# KONNEKTING_HW1_1_Rev0.net
KiCad netlist of a schematic drawn in EAGLE
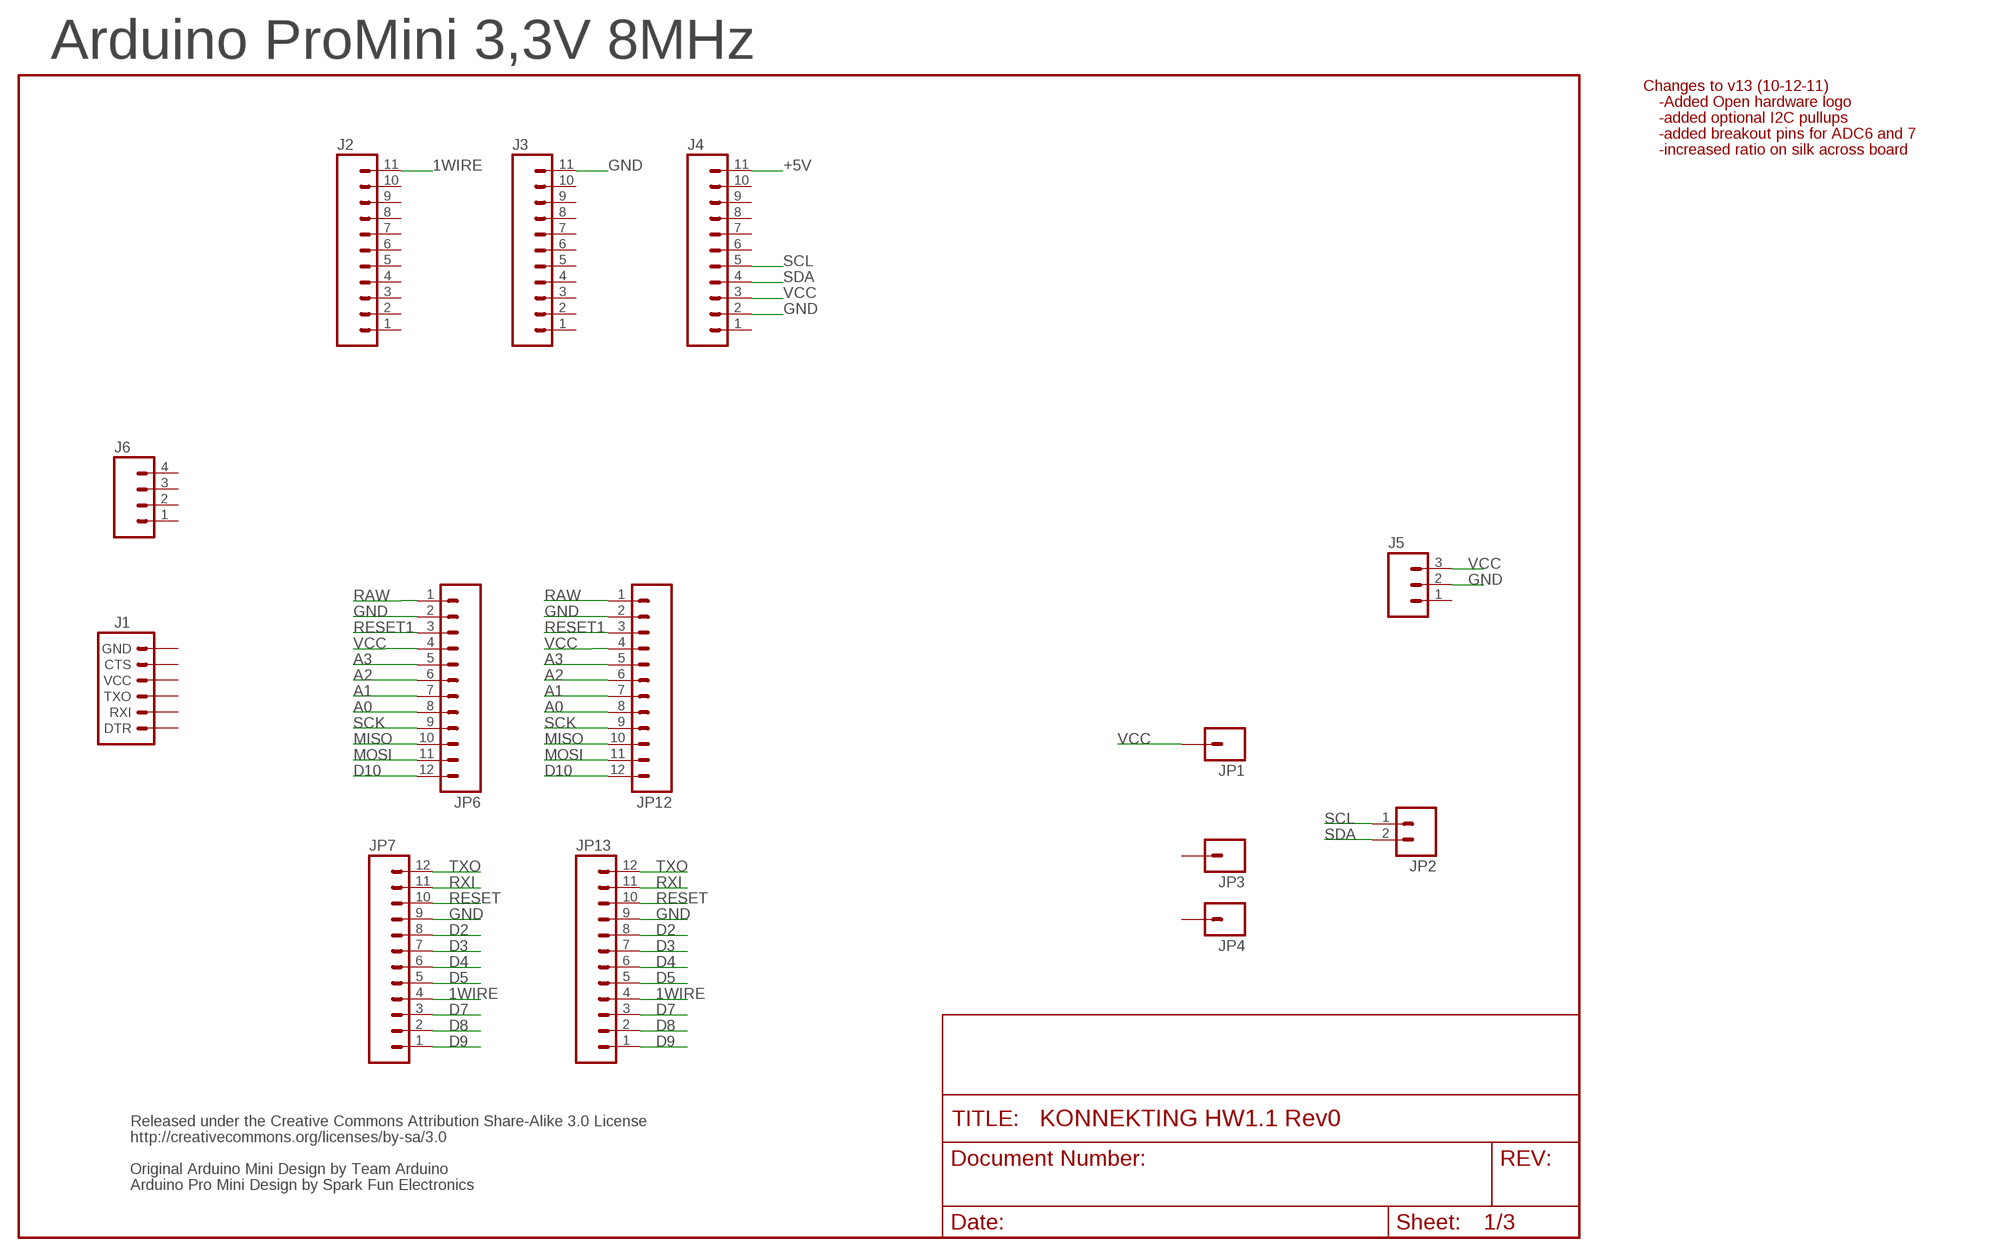
[diagram p0: schematic, sheet 1]
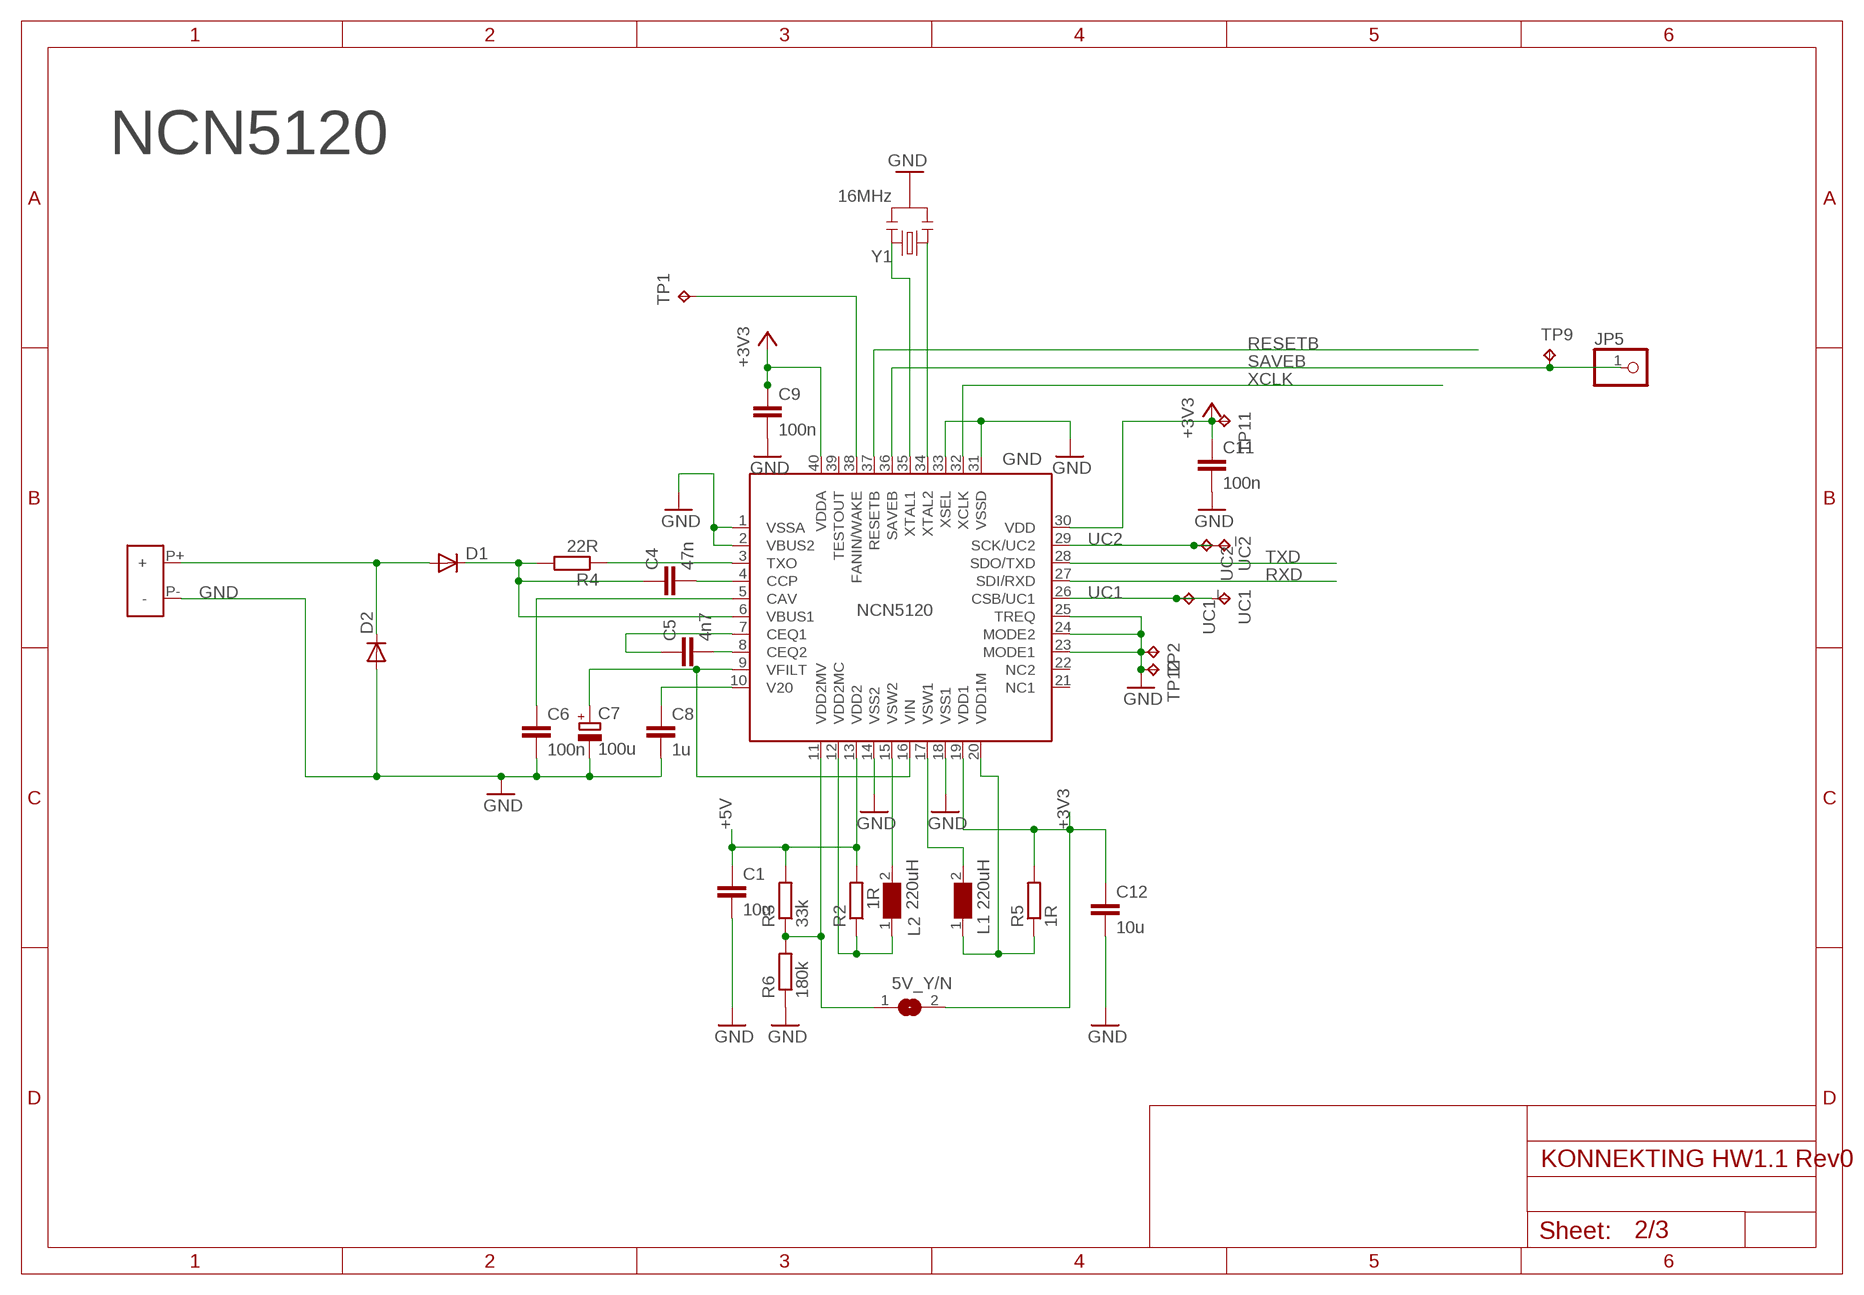
[diagram p1: schematic, sheet 2]
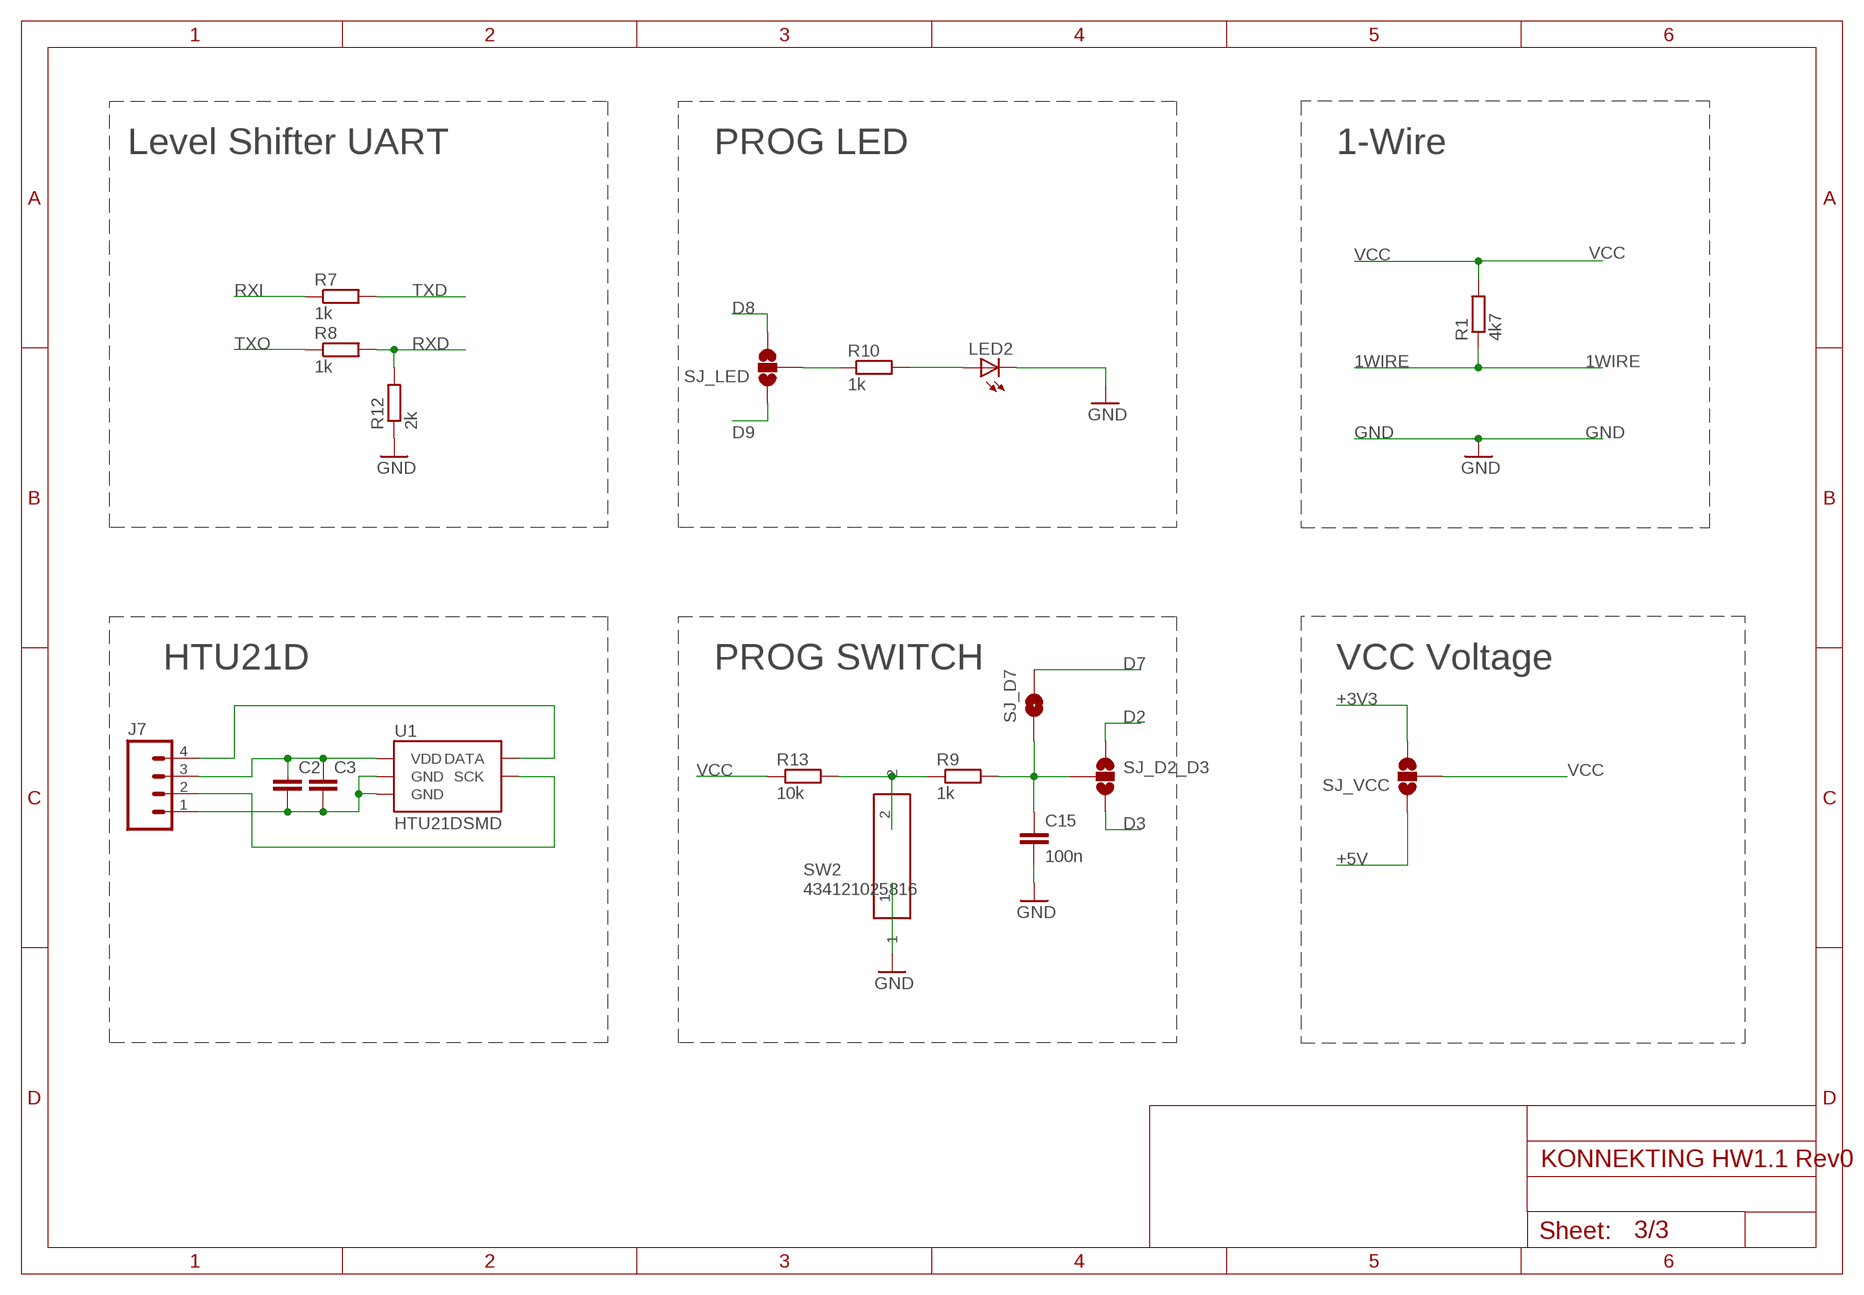
[diagram p2: schematic, sheet 3]

(export (version "E")
  (design (tool "Eeschema 10.0.6"))
  (components
    (comp (ref "J1")
      (value "ARDUINO_SERIAL_PROGRAMPTH")
      (footprint "eagle-import:1X06")
      (libsource (lib "eagle-import") (part "ARDUINO_SERIAL_PROGRAMPTH"))
    )
    (comp (ref "J2")
      (value "M11PTH")
      (footprint "eagle-import:1X11")
      (libsource (lib "eagle-import") (part "M11PTH"))
    )
    (comp (ref "J3")
      (value "M11PTH")
      (footprint "eagle-import:1X11")
      (libsource (lib "eagle-import") (part "M11PTH"))
    )
    (comp (ref "J4")
      (value "M11PTH")
      (footprint "eagle-import:1X11")
      (libsource (lib "eagle-import") (part "M11PTH"))
    )
    (comp (ref "J5")
      (value "M03PTH")
      (footprint "eagle-import:1X03")
      (libsource (lib "eagle-import") (part "M03PTH"))
    )
    (comp (ref "J6")
      (value "M04PTH")
      (footprint "eagle-import:1X04")
      (libsource (lib "eagle-import") (part "M04PTH"))
    )
    (comp (ref "JP1")
      (value "M01PTH")
      (footprint "eagle-import:1X01")
      (libsource (lib "eagle-import") (part "M01PTH"))
    )
    (comp (ref "JP2")
      (value "M02PTH")
      (footprint "eagle-import:1X02")
      (libsource (lib "eagle-import") (part "M02PTH"))
    )
    (comp (ref "JP3")
      (value "M01PTH")
      (footprint "eagle-import:1X01")
      (libsource (lib "eagle-import") (part "M01PTH"))
    )
    (comp (ref "JP4")
      (value "M01PTH")
      (footprint "eagle-import:1X01")
      (libsource (lib "eagle-import") (part "M01PTH"))
    )
    (comp (ref "JP6")
      (value "M12PTH")
      (footprint "eagle-import:1X12")
      (libsource (lib "eagle-import") (part "M12PTH"))
    )
    (comp (ref "JP7")
      (value "M12PTH")
      (footprint "eagle-import:1X12")
      (libsource (lib "eagle-import") (part "M12PTH"))
    )
    (comp (ref "JP12")
      (value "M12PTH")
      (footprint "eagle-import:1X12")
      (libsource (lib "eagle-import") (part "M12PTH"))
    )
    (comp (ref "JP13")
      (value "M12PTH")
      (footprint "eagle-import:1X12")
      (libsource (lib "eagle-import") (part "M12PTH"))
    )
    (comp (ref "C2")
      (value "CAP0603-CAP")
      (footprint "eagle-import:0603-CAP")
      (libsource (lib "eagle-import") (part "CAP0603-CAP"))
    )
    (comp (ref "C3")
      (value "CAP0603-CAP")
      (footprint "eagle-import:0603-CAP")
      (libsource (lib "eagle-import") (part "CAP0603-CAP"))
    )
    (comp (ref "C15")
      (value "100n")
      (footprint "eagle-import:C0603")
      (libsource (lib "eagle-import") (part "C-EUC0603"))
    )
    (comp (ref "J7")
      (value "M04PTH")
      (footprint "eagle-import:1X04")
      (libsource (lib "eagle-import") (part "M04PTH"))
    )
    (comp (ref "LED2")
      (value "LEDCHIP-LED0805")
      (footprint "eagle-import:CHIP-LED0805")
      (libsource (lib "eagle-import") (part "LEDCHIP-LED0805"))
    )
    (comp (ref "R1")
      (value "4k7")
      (footprint "eagle-import:R0603")
      (libsource (lib "eagle-import") (part "R-EU_R0603"))
    )
    (comp (ref "R7")
      (value "1k")
      (footprint "eagle-import:R0805")
      (libsource (lib "eagle-import") (part "R-EU_R0805"))
    )
    (comp (ref "R8")
      (value "1k")
      (footprint "eagle-import:R0805")
      (libsource (lib "eagle-import") (part "R-EU_R0805"))
    )
    (comp (ref "R9")
      (value "1k")
      (footprint "eagle-import:R0603")
      (libsource (lib "eagle-import") (part "R-EU_R0603"))
    )
    (comp (ref "R10")
      (value "1k")
      (footprint "eagle-import:R0603")
      (libsource (lib "eagle-import") (part "R-EU_R0603"))
    )
    (comp (ref "R12")
      (value "2k")
      (footprint "eagle-import:R0805")
      (libsource (lib "eagle-import") (part "R-EU_R0805"))
    )
    (comp (ref "R13")
      (value "10k")
      (footprint "eagle-import:R0603")
      (libsource (lib "eagle-import") (part "R-EU_R0603"))
    )
    (comp (ref "SJ_D2_D3")
      (value "SOLDERJUMPER_2WAYS")
      (footprint "eagle-import:SJ_3")
      (libsource (lib "eagle-import") (part "SOLDERJUMPER_2WAYS"))
    )
    (comp (ref "SJ_D7")
      (value "SOLDERJUMPERNO")
      (footprint "eagle-import:SJ_2S-NO")
      (libsource (lib "eagle-import") (part "SOLDERJUMPERNO"))
    )
    (comp (ref "SJ_LED")
      (value "SOLDERJUMPER_2WAYS")
      (footprint "eagle-import:SJ_3")
      (libsource (lib "eagle-import") (part "SOLDERJUMPER_2WAYS"))
    )
    (comp (ref "SJ_VCC")
      (value "SOLDERJUMPER_2WAYS")
      (footprint "eagle-import:SJ_3")
      (libsource (lib "eagle-import") (part "SOLDERJUMPER_2WAYS"))
    )
    (comp (ref "SW2")
      (value "434121025816")
      (footprint "eagle-import:434121025816")
      (libsource (lib "eagle-import") (part "434121025816"))
    )
    (comp (ref "U1")
      (value "HTU21DSMD")
      (footprint "eagle-import:HTU21D")
      (libsource (lib "eagle-import") (part "HTU21DSMD"))
    )
    (comp (ref "5V_Y/N")
      (value "SJ")
      (footprint "eagle-import:SJ")
      (libsource (lib "eagle-import") (part "SJ"))
    )
    (comp (ref "C1")
      (value "10u")
      (footprint "eagle-import:C0805")
      (libsource (lib "eagle-import") (part "C-EUC0805"))
    )
    (comp (ref "C4")
      (value "47n")
      (footprint "eagle-import:C0603")
      (libsource (lib "eagle-import") (part "C-EUC0603"))
    )
    (comp (ref "C5")
      (value "4n7")
      (footprint "eagle-import:C0603")
      (libsource (lib "eagle-import") (part "C-EUC0603"))
    )
    (comp (ref "C6")
      (value "100n")
      (footprint "eagle-import:C0603")
      (libsource (lib "eagle-import") (part "C-EUC0603"))
    )
    (comp (ref "C7")
      (value "100u")
      (footprint "eagle-import:UD-6,3X7,7_NICHICON")
      (libsource (lib "eagle-import") (part "CPOL-EUUD-6,3X7,7"))
    )
    (comp (ref "C8")
      (value "1u")
      (footprint "eagle-import:C0603")
      (libsource (lib "eagle-import") (part "C-EUC0603"))
    )
    (comp (ref "C9")
      (value "100n")
      (footprint "eagle-import:C0603")
      (libsource (lib "eagle-import") (part "C-EUC0603"))
    )
    (comp (ref "C11")
      (value "100n")
      (footprint "eagle-import:C0603")
      (libsource (lib "eagle-import") (part "C-EUC0603"))
    )
    (comp (ref "C12")
      (value "10u")
      (footprint "eagle-import:C0805")
      (libsource (lib "eagle-import") (part "C-EUC0805"))
    )
    (comp (ref "D1")
      (value "DIODESMA-ALT")
      (footprint "eagle-import:SMA-DIODE_ALT")
      (libsource (lib "eagle-import") (part "DIODESMA-ALT"))
    )
    (comp (ref "D2")
      (value "DIODESMA-ALT")
      (footprint "eagle-import:SMA-DIODE_ALT")
      (libsource (lib "eagle-import") (part "DIODESMA-ALT"))
    )
    (comp (ref "GND")
      (value "NCN5120_KNX_TRANSCEIVER")
      (footprint "eagle-import:QFN40")
      (libsource (lib "eagle-import") (part "NCN5120_KNX_TRANSCEIVER"))
    )
    (comp (ref "JP5")
      (value "PINHD-1X1")
      (footprint "eagle-import:1X01")
      (libsource (lib "eagle-import") (part "PINHD-1X1"))
    )
    (comp (ref "L1")
      (value "220uH")
      (footprint "eagle-import:WE-PD2_7850")
      (libsource (lib "eagle-import") (part "WE-PD2_7850"))
    )
    (comp (ref "L2")
      (value "220uH")
      (footprint "eagle-import:WE-PD2_7850")
      (libsource (lib "eagle-import") (part "WE-PD2_7850"))
    )
    (comp (ref "R2")
      (value "1R")
      (footprint "eagle-import:R0603")
      (libsource (lib "eagle-import") (part "R-EU_R0603"))
    )
    (comp (ref "R3")
      (value "33k")
      (footprint "eagle-import:R0603")
      (libsource (lib "eagle-import") (part "R-EU_R0603"))
    )
    (comp (ref "R4")
      (value "22R")
      (footprint "eagle-import:R2512")
      (libsource (lib "eagle-import") (part "R-EU_R2512"))
    )
    (comp (ref "R5")
      (value "1R")
      (footprint "eagle-import:R0603")
      (libsource (lib "eagle-import") (part "R-EU_R0603"))
    )
    (comp (ref "R6")
      (value "180k")
      (footprint "eagle-import:R0603")
      (libsource (lib "eagle-import") (part "R-EU_R0603"))
    )
    (comp (ref "TP1")
      (value "TPTP10SQ")
      (footprint "eagle-import:TP10SQ")
      (libsource (lib "eagle-import") (part "TPTP10SQ"))
    )
    (comp (ref "TP2")
      (value "TPTP09SQ")
      (footprint "eagle-import:TP09SQ")
      (libsource (lib "eagle-import") (part "TPTP09SQ"))
    )
    (comp (ref "TP9")
      (value "TPTP10SQ")
      (footprint "eagle-import:TP10SQ")
      (libsource (lib "eagle-import") (part "TPTP10SQ"))
    )
    (comp (ref "TP11")
      (value "TPTP09SQ")
      (footprint "eagle-import:TP09SQ")
      (libsource (lib "eagle-import") (part "TPTP09SQ"))
    )
    (comp (ref "TP12")
      (value "TPTP09SQ")
      (footprint "eagle-import:TP09SQ")
      (libsource (lib "eagle-import") (part "TPTP09SQ"))
    )
    (comp (ref "U$2")
      (value "KNX_KLEMME")
      (footprint "eagle-import:KNX_KLEMME")
      (libsource (lib "eagle-import") (part "KNX_KLEMME"))
    )
    (comp (ref "UC1")
      (value "TPTP09SQ")
      (footprint "eagle-import:TP09SQ")
      (libsource (lib "eagle-import") (part "TPTP09SQ"))
    )
    (comp (ref "UC1_")
      (value "TPTP09SQ")
      (footprint "eagle-import:TP09SQ")
      (libsource (lib "eagle-import") (part "TPTP09SQ"))
    )
    (comp (ref "UC2")
      (value "TPTP09SQ")
      (footprint "eagle-import:TP09SQ")
      (libsource (lib "eagle-import") (part "TPTP09SQ"))
    )
    (comp (ref "UC2_")
      (value "TPTP09SQ")
      (footprint "eagle-import:TP09SQ")
      (libsource (lib "eagle-import") (part "TPTP09SQ"))
    )
    (comp (ref "Y1")
      (value "16MHz")
      (footprint "eagle-import:RESONATOR-SMD")
      (libsource (lib "eagle-import") (part "RESONATORSMD"))
    )
  )
  (nets
    (net (code "1") (name "+3V3") (class "Default")
      (node (ref "5V_Y/N") (pin "2") (pinfunction "2_2") (pintype "passive"))
      (node (ref "C11") (pin "1") (pinfunction "1_1") (pintype "passive"))
      (node (ref "C12") (pin "1") (pinfunction "1_1") (pintype "passive"))
      (node (ref "C9") (pin "1") (pinfunction "1_1") (pintype "passive"))
      (node (ref "GND") (pin "19") (pinfunction "VDD1_19") (pintype "bidirectional"))
      (node (ref "GND") (pin "30") (pinfunction "VDD_30") (pintype "bidirectional"))
      (node (ref "GND") (pin "40") (pinfunction "VDDA_40") (pintype "bidirectional"))
      (node (ref "R5") (pin "2") (pinfunction "2_2") (pintype "passive"))
      (node (ref "SJ_VCC") (pin "3") (pinfunction "3_3") (pintype "passive"))
      (node (ref "TP11") (pin "TP") (pinfunction "TP_TP") (pintype "input"))
    )
    (net (code "2") (name "+5V") (class "Default")
      (node (ref "C1") (pin "1") (pinfunction "1_1") (pintype "passive"))
      (node (ref "GND") (pin "13") (pinfunction "VDD2_13") (pintype "bidirectional"))
      (node (ref "J4") (pin "11") (pinfunction "11_11") (pintype "passive"))
      (node (ref "R2") (pin "2") (pinfunction "2_2") (pintype "passive"))
      (node (ref "R3") (pin "2") (pinfunction "2_2") (pintype "passive"))
      (node (ref "SJ_VCC") (pin "1") (pinfunction "1_1") (pintype "passive"))
    )
    (net (code "3") (name "1WIRE") (class "Default")
      (node (ref "J2") (pin "11") (pinfunction "11_11") (pintype "passive"))
      (node (ref "JP13") (pin "4") (pinfunction "4_4") (pintype "passive"))
      (node (ref "JP7") (pin "4") (pinfunction "4_4") (pintype "passive"))
      (node (ref "R1") (pin "1") (pinfunction "1_1") (pintype "passive"))
    )
    (net (code "4") (name "A0") (class "Default")
      (node (ref "JP12") (pin "8") (pinfunction "8_8") (pintype "passive"))
      (node (ref "JP6") (pin "8") (pinfunction "8_8") (pintype "passive"))
    )
    (net (code "5") (name "A1") (class "Default")
      (node (ref "JP12") (pin "7") (pinfunction "7_7") (pintype "passive"))
      (node (ref "JP6") (pin "7") (pinfunction "7_7") (pintype "passive"))
    )
    (net (code "6") (name "A2") (class "Default")
      (node (ref "JP12") (pin "6") (pinfunction "6_6") (pintype "passive"))
      (node (ref "JP6") (pin "6") (pinfunction "6_6") (pintype "passive"))
    )
    (net (code "7") (name "A3") (class "Default")
      (node (ref "JP12") (pin "5") (pinfunction "5_5") (pintype "passive"))
      (node (ref "JP6") (pin "5") (pinfunction "5_5") (pintype "passive"))
    )
    (net (code "8") (name "D2") (class "Default")
      (node (ref "JP13") (pin "8") (pinfunction "8_8") (pintype "passive"))
      (node (ref "JP7") (pin "8") (pinfunction "8_8") (pintype "passive"))
      (node (ref "SJ_D2_D3") (pin "1") (pinfunction "1_1") (pintype "passive"))
    )
    (net (code "9") (name "D3") (class "Default")
      (node (ref "JP13") (pin "7") (pinfunction "7_7") (pintype "passive"))
      (node (ref "JP7") (pin "7") (pinfunction "7_7") (pintype "passive"))
      (node (ref "SJ_D2_D3") (pin "3") (pinfunction "3_3") (pintype "passive"))
    )
    (net (code "10") (name "D4") (class "Default")
      (node (ref "JP13") (pin "6") (pinfunction "6_6") (pintype "passive"))
      (node (ref "JP7") (pin "6") (pinfunction "6_6") (pintype "passive"))
    )
    (net (code "11") (name "D5") (class "Default")
      (node (ref "JP13") (pin "5") (pinfunction "5_5") (pintype "passive"))
      (node (ref "JP7") (pin "5") (pinfunction "5_5") (pintype "passive"))
    )
    (net (code "12") (name "D7") (class "Default")
      (node (ref "JP13") (pin "3") (pinfunction "3_3") (pintype "passive"))
      (node (ref "JP7") (pin "3") (pinfunction "3_3") (pintype "passive"))
      (node (ref "SJ_D7") (pin "2") (pinfunction "2_2") (pintype "passive"))
    )
    (net (code "13") (name "D8") (class "Default")
      (node (ref "JP13") (pin "2") (pinfunction "2_2") (pintype "passive"))
      (node (ref "JP7") (pin "2") (pinfunction "2_2") (pintype "passive"))
      (node (ref "SJ_LED") (pin "3") (pinfunction "3_3") (pintype "passive"))
    )
    (net (code "14") (name "D9") (class "Default")
      (node (ref "JP13") (pin "1") (pinfunction "1_1") (pintype "passive"))
      (node (ref "JP7") (pin "1") (pinfunction "1_1") (pintype "passive"))
      (node (ref "SJ_LED") (pin "1") (pinfunction "1_1") (pintype "passive"))
    )
    (net (code "15") (name "D10") (class "Default")
      (node (ref "JP12") (pin "12") (pinfunction "12_12") (pintype "passive"))
      (node (ref "JP6") (pin "12") (pinfunction "12_12") (pintype "passive"))
    )
    (net (code "16") (name "GND") (class "Default")
      (node (ref "C1") (pin "2") (pinfunction "2_2") (pintype "passive"))
      (node (ref "C11") (pin "2") (pinfunction "2_2") (pintype "passive"))
      (node (ref "C12") (pin "2") (pinfunction "2_2") (pintype "passive"))
      (node (ref "C15") (pin "2") (pinfunction "2_2") (pintype "passive"))
      (node (ref "C6") (pin "2") (pinfunction "2_2") (pintype "passive"))
      (node (ref "C7") (pin "-") (pinfunction "-_-") (pintype "passive"))
      (node (ref "C8") (pin "2") (pinfunction "2_2") (pintype "passive"))
      (node (ref "C9") (pin "2") (pinfunction "2_2") (pintype "passive"))
      (node (ref "D2") (pin "A") (pinfunction "A_A") (pintype "passive"))
      (node (ref "GND") (pin "1") (pinfunction "VSSA_1") (pintype "bidirectional"))
      (node (ref "GND") (pin "14") (pinfunction "VSS2_14") (pintype "bidirectional"))
      (node (ref "GND") (pin "18") (pinfunction "VSS1_18") (pintype "bidirectional"))
      (node (ref "GND") (pin "2") (pinfunction "VBUS2_2") (pintype "bidirectional"))
      (node (ref "GND") (pin "23") (pinfunction "MODE1_23") (pintype "bidirectional"))
      (node (ref "GND") (pin "24") (pinfunction "MODE2_24") (pintype "bidirectional"))
      (node (ref "GND") (pin "25") (pinfunction "TREQ_25") (pintype "bidirectional"))
      (node (ref "GND") (pin "31") (pinfunction "VSSD_31") (pintype "bidirectional"))
      (node (ref "GND") (pin "33") (pinfunction "XSEL_33") (pintype "bidirectional"))
      (node (ref "J3") (pin "11") (pinfunction "11_11") (pintype "passive"))
      (node (ref "J4") (pin "2") (pinfunction "2_2") (pintype "passive"))
      (node (ref "J5") (pin "2") (pinfunction "2_2") (pintype "passive"))
      (node (ref "JP12") (pin "2") (pinfunction "2_2") (pintype "passive"))
      (node (ref "JP13") (pin "9") (pinfunction "9_9") (pintype "passive"))
      (node (ref "JP6") (pin "2") (pinfunction "2_2") (pintype "passive"))
      (node (ref "JP7") (pin "9") (pinfunction "9_9") (pintype "passive"))
      (node (ref "LED2") (pin "C") (pinfunction "C_C") (pintype "passive"))
      (node (ref "R12") (pin "1") (pinfunction "1_1") (pintype "passive"))
      (node (ref "R6") (pin "1") (pinfunction "1_1") (pintype "passive"))
      (node (ref "SW2") (pin "1") (pinfunction "1_1") (pintype "bidirectional"))
      (node (ref "TP12") (pin "TP") (pinfunction "TP_TP") (pintype "input"))
      (node (ref "TP2") (pin "TP") (pinfunction "TP_TP") (pintype "input"))
      (node (ref "U$2") (pin "P-") (pinfunction "-_P-") (pintype "bidirectional"))
      (node (ref "Y1") (pin "2") (pinfunction "2_2") (pintype "passive"))
    )
    (net (code "17") (name "MISO") (class "Default")
      (node (ref "JP12") (pin "10") (pinfunction "10_10") (pintype "passive"))
      (node (ref "JP6") (pin "10") (pinfunction "10_10") (pintype "passive"))
    )
    (net (code "18") (name "MOSI") (class "Default")
      (node (ref "JP12") (pin "11") (pinfunction "11_11") (pintype "passive"))
      (node (ref "JP6") (pin "11") (pinfunction "11_11") (pintype "passive"))
    )
    (net (code "19") (name "Net-(C2-Pad1)") (class "Default")
      (node (ref "C2") (pin "1") (pinfunction "1_1") (pintype "passive"))
      (node (ref "C3") (pin "1") (pinfunction "1_1") (pintype "passive"))
      (node (ref "J7") (pin "3") (pinfunction "3_3") (pintype "passive"))
      (node (ref "U1") (pin "VDD") (pinfunction "VDD_VDD") (pintype "power_in"))
    )
    (net (code "20") (name "Net-(C2-Pad2)") (class "Default")
      (node (ref "C2") (pin "2") (pinfunction "2_2") (pintype "passive"))
      (node (ref "C3") (pin "2") (pinfunction "2_2") (pintype "passive"))
      (node (ref "J7") (pin "1") (pinfunction "1_1") (pintype "passive"))
      (node (ref "U1") (pin "7") (pinfunction "GND_7") (pintype "power_in"))
      (node (ref "U1") (pin "GND") (pinfunction "GND_GND") (pintype "power_in"))
    )
    (net (code "21") (name "Net-(C15-Pad1)") (class "Default")
      (node (ref "C15") (pin "1") (pinfunction "1_1") (pintype "passive"))
      (node (ref "R9") (pin "2") (pinfunction "2_2") (pintype "passive"))
      (node (ref "SJ_D2_D3") (pin "2") (pinfunction "2_2") (pintype "passive"))
      (node (ref "SJ_D7") (pin "1") (pinfunction "1_1") (pintype "passive"))
    )
    (net (code "22") (name "Net-(GND-CAV)") (class "Default")
      (node (ref "C6") (pin "1") (pinfunction "1_1") (pintype "passive"))
      (node (ref "GND") (pin "5") (pinfunction "CAV_5") (pintype "bidirectional"))
    )
    (net (code "23") (name "Net-(GND-CCP)") (class "Default")
      (node (ref "C4") (pin "2") (pinfunction "2_2") (pintype "passive"))
      (node (ref "GND") (pin "4") (pinfunction "CCP_4") (pintype "bidirectional"))
    )
    (net (code "24") (name "Net-(GND-CEQ1)") (class "Default")
      (node (ref "C5") (pin "1") (pinfunction "1_1") (pintype "passive"))
      (node (ref "GND") (pin "7") (pinfunction "CEQ1_7") (pintype "bidirectional"))
    )
    (net (code "25") (name "Net-(GND-CEQ2)") (class "Default")
      (node (ref "C5") (pin "2") (pinfunction "2_2") (pintype "passive"))
      (node (ref "GND") (pin "8") (pinfunction "CEQ2_8") (pintype "bidirectional"))
    )
    (net (code "26") (name "Net-(GND-FANIN{slash}WAKE)") (class "Default")
      (node (ref "GND") (pin "38") (pinfunction "FANIN/WAKE_38") (pintype "bidirectional"))
      (node (ref "TP1") (pin "TP") (pinfunction "TP_TP") (pintype "input"))
    )
    (net (code "27") (name "Net-(GND-TXO)") (class "Default")
      (node (ref "GND") (pin "3") (pinfunction "TXO_3") (pintype "bidirectional"))
      (node (ref "R4") (pin "1") (pinfunction "1_1") (pintype "passive"))
    )
    (net (code "28") (name "Net-(GND-V20)") (class "Default")
      (node (ref "C8") (pin "1") (pinfunction "1_1") (pintype "passive"))
      (node (ref "GND") (pin "10") (pinfunction "V20_10") (pintype "bidirectional"))
    )
    (net (code "29") (name "Net-(GND-VBUS1)") (class "Default")
      (node (ref "C4") (pin "1") (pinfunction "1_1") (pintype "passive"))
      (node (ref "D1") (pin "C") (pinfunction "C_C") (pintype "passive"))
      (node (ref "GND") (pin "6") (pinfunction "VBUS1_6") (pintype "bidirectional"))
      (node (ref "R4") (pin "2") (pinfunction "2_2") (pintype "passive"))
    )
    (net (code "30") (name "Net-(GND-VDD1M)") (class "Default")
      (node (ref "GND") (pin "20") (pinfunction "VDD1M_20") (pintype "bidirectional"))
      (node (ref "L1") (pin "1") (pinfunction "1_1") (pintype "passive"))
      (node (ref "R5") (pin "1") (pinfunction "1_1") (pintype "passive"))
    )
    (net (code "31") (name "Net-(GND-VDD2MC)") (class "Default")
      (node (ref "GND") (pin "12") (pinfunction "VDD2MC_12") (pintype "bidirectional"))
      (node (ref "L2") (pin "1") (pinfunction "1_1") (pintype "passive"))
      (node (ref "R2") (pin "1") (pinfunction "1_1") (pintype "passive"))
    )
    (net (code "32") (name "Net-(GND-VDD2MV)") (class "Default")
      (node (ref "5V_Y/N") (pin "1") (pinfunction "1_1") (pintype "passive"))
      (node (ref "GND") (pin "11") (pinfunction "VDD2MV_11") (pintype "bidirectional"))
      (node (ref "R3") (pin "1") (pinfunction "1_1") (pintype "passive"))
      (node (ref "R6") (pin "2") (pinfunction "2_2") (pintype "passive"))
    )
    (net (code "33") (name "Net-(GND-VFILT)") (class "Default")
      (node (ref "C7") (pin "+") (pinfunction "+_+") (pintype "passive"))
      (node (ref "GND") (pin "16") (pinfunction "VIN_16") (pintype "bidirectional"))
      (node (ref "GND") (pin "9") (pinfunction "VFILT_9") (pintype "bidirectional"))
    )
    (net (code "34") (name "Net-(GND-VSW1)") (class "Default")
      (node (ref "GND") (pin "17") (pinfunction "VSW1_17") (pintype "bidirectional"))
      (node (ref "L1") (pin "2") (pinfunction "2_2") (pintype "passive"))
    )
    (net (code "35") (name "Net-(GND-VSW2)") (class "Default")
      (node (ref "GND") (pin "15") (pinfunction "VSW2_15") (pintype "bidirectional"))
      (node (ref "L2") (pin "2") (pinfunction "2_2") (pintype "passive"))
    )
    (net (code "36") (name "Net-(GND-XTAL1)") (class "Default")
      (node (ref "GND") (pin "35") (pinfunction "XTAL1_35") (pintype "bidirectional"))
      (node (ref "Y1") (pin "3") (pinfunction "3_3") (pintype "passive"))
    )
    (net (code "37") (name "Net-(GND-XTAL2)") (class "Default")
      (node (ref "GND") (pin "34") (pinfunction "XTAL2_34") (pintype "bidirectional"))
      (node (ref "Y1") (pin "1") (pinfunction "1_1") (pintype "passive"))
    )
    (net (code "38") (name "Net-(J7-Pad2)") (class "Default")
      (node (ref "J7") (pin "2") (pinfunction "2_2") (pintype "passive"))
      (node (ref "U1") (pin "SCK") (pinfunction "SCK_SCK") (pintype "input"))
    )
    (net (code "39") (name "Net-(J7-Pad4)") (class "Default")
      (node (ref "J7") (pin "4") (pinfunction "4_4") (pintype "passive"))
      (node (ref "U1") (pin "DATA") (pinfunction "DATA_DATA") (pintype "bidirectional"))
    )
    (net (code "40") (name "Net-(LED2-PadA)") (class "Default")
      (node (ref "LED2") (pin "A") (pinfunction "A_A") (pintype "passive"))
      (node (ref "R10") (pin "2") (pinfunction "2_2") (pintype "passive"))
    )
    (net (code "41") (name "Net-(R10-Pad1)") (class "Default")
      (node (ref "R10") (pin "1") (pinfunction "1_1") (pintype "passive"))
      (node (ref "SJ_LED") (pin "2") (pinfunction "2_2") (pintype "passive"))
    )
    (net (code "42") (name "Net-(R13-Pad2)") (class "Default")
      (node (ref "R13") (pin "2") (pinfunction "2_2") (pintype "passive"))
      (node (ref "R9") (pin "1") (pinfunction "1_1") (pintype "passive"))
      (node (ref "SW2") (pin "2") (pinfunction "2_2") (pintype "bidirectional"))
    )
    (net (code "43") (name "Net-(U$2-+)") (class "Default")
      (node (ref "D1") (pin "A") (pinfunction "A_A") (pintype "passive"))
      (node (ref "D2") (pin "C") (pinfunction "C_C") (pintype "passive"))
      (node (ref "U$2") (pin "P+") (pinfunction "+_P+") (pintype "bidirectional"))
    )
    (net (code "44") (name "RAW") (class "Default")
      (node (ref "JP12") (pin "1") (pinfunction "1_1") (pintype "passive"))
      (node (ref "JP6") (pin "1") (pinfunction "1_1") (pintype "passive"))
    )
    (net (code "45") (name "RESET") (class "Default")
      (node (ref "JP13") (pin "10") (pinfunction "10_10") (pintype "passive"))
      (node (ref "JP7") (pin "10") (pinfunction "10_10") (pintype "passive"))
    )
    (net (code "46") (name "RESET1") (class "Default")
      (node (ref "JP12") (pin "3") (pinfunction "3_3") (pintype "passive"))
      (node (ref "JP6") (pin "3") (pinfunction "3_3") (pintype "passive"))
    )
    (net (code "47") (name "RESETB") (class "Default")
      (node (ref "GND") (pin "37") (pinfunction "RESETB_37") (pintype "bidirectional"))
    )
    (net (code "48") (name "RXD") (class "Default")
      (node (ref "GND") (pin "27") (pinfunction "SDI/RXD_27") (pintype "bidirectional"))
      (node (ref "R12") (pin "2") (pinfunction "2_2") (pintype "passive"))
      (node (ref "R8") (pin "2") (pinfunction "2_2") (pintype "passive"))
    )
    (net (code "49") (name "RXI") (class "Default")
      (node (ref "JP13") (pin "11") (pinfunction "11_11") (pintype "passive"))
      (node (ref "JP7") (pin "11") (pinfunction "11_11") (pintype "passive"))
      (node (ref "R7") (pin "1") (pinfunction "1_1") (pintype "passive"))
    )
    (net (code "50") (name "SAVEB") (class "Default")
      (node (ref "GND") (pin "36") (pinfunction "SAVEB_36") (pintype "bidirectional"))
      (node (ref "JP5") (pin "1") (pinfunction "1_1") (pintype "passive"))
      (node (ref "TP9") (pin "TP") (pinfunction "TP_TP") (pintype "input"))
    )
    (net (code "51") (name "SCK") (class "Default")
      (node (ref "JP12") (pin "9") (pinfunction "9_9") (pintype "passive"))
      (node (ref "JP6") (pin "9") (pinfunction "9_9") (pintype "passive"))
    )
    (net (code "52") (name "SCL") (class "Default")
      (node (ref "J4") (pin "5") (pinfunction "5_5") (pintype "passive"))
      (node (ref "JP2") (pin "1") (pinfunction "1_1") (pintype "passive"))
    )
    (net (code "53") (name "SDA") (class "Default")
      (node (ref "J4") (pin "4") (pinfunction "4_4") (pintype "passive"))
      (node (ref "JP2") (pin "2") (pinfunction "2_2") (pintype "passive"))
    )
    (net (code "54") (name "TXD") (class "Default")
      (node (ref "GND") (pin "28") (pinfunction "SDO/TXD_28") (pintype "bidirectional"))
      (node (ref "R7") (pin "2") (pinfunction "2_2") (pintype "passive"))
    )
    (net (code "55") (name "TXO") (class "Default")
      (node (ref "JP13") (pin "12") (pinfunction "12_12") (pintype "passive"))
      (node (ref "JP7") (pin "12") (pinfunction "12_12") (pintype "passive"))
      (node (ref "R8") (pin "1") (pinfunction "1_1") (pintype "passive"))
    )
    (net (code "56") (name "UC1") (class "Default")
      (node (ref "GND") (pin "26") (pinfunction "CSB/UC1_26") (pintype "bidirectional"))
      (node (ref "UC1") (pin "TP") (pinfunction "TP_TP") (pintype "input"))
      (node (ref "UC1_") (pin "TP") (pinfunction "TP_TP") (pintype "input"))
    )
    (net (code "57") (name "UC2") (class "Default")
      (node (ref "GND") (pin "29") (pinfunction "SCK/UC2_29") (pintype "bidirectional"))
      (node (ref "UC2") (pin "TP") (pinfunction "TP_TP") (pintype "input"))
      (node (ref "UC2_") (pin "TP") (pinfunction "TP_TP") (pintype "input"))
    )
    (net (code "58") (name "VCC") (class "Default")
      (node (ref "J4") (pin "3") (pinfunction "3_3") (pintype "passive"))
      (node (ref "J5") (pin "3") (pinfunction "3_3") (pintype "passive"))
      (node (ref "JP1") (pin "1") (pinfunction "1_1") (pintype "passive"))
      (node (ref "JP12") (pin "4") (pinfunction "4_4") (pintype "passive"))
      (node (ref "JP6") (pin "4") (pinfunction "4_4") (pintype "passive"))
      (node (ref "R1") (pin "2") (pinfunction "2_2") (pintype "passive"))
      (node (ref "R13") (pin "1") (pinfunction "1_1") (pintype "passive"))
      (node (ref "SJ_VCC") (pin "2") (pinfunction "2_2") (pintype "passive"))
    )
    (net (code "59") (name "XCLK") (class "Default")
      (node (ref "GND") (pin "32") (pinfunction "XCLK_32") (pintype "bidirectional"))
    )
    (net (code "60") (name "unconnected-(GND-NC1-Pad21)") (class "Default")
      (node (ref "GND") (pin "21") (pinfunction "NC1_21") (pintype "bidirectional"))
    )
    (net (code "61") (name "unconnected-(GND-NC2-Pad22)") (class "Default")
      (node (ref "GND") (pin "22") (pinfunction "NC2_22") (pintype "bidirectional"))
    )
    (net (code "62") (name "unconnected-(GND-TESTOUT-Pad39)") (class "Default")
      (node (ref "GND") (pin "39") (pinfunction "TESTOUT_39") (pintype "bidirectional"))
    )
    (net (code "63") (name "unconnected-(J1-CTS-Pad5)") (class "Default")
      (node (ref "J1") (pin "5") (pinfunction "CTS_5") (pintype "passive"))
    )
    (net (code "64") (name "unconnected-(J1-DTR-Pad1)") (class "Default")
      (node (ref "J1") (pin "1") (pinfunction "DTR_1") (pintype "passive"))
    )
    (net (code "65") (name "unconnected-(J1-GND-Pad6)") (class "Default")
      (node (ref "J1") (pin "6") (pinfunction "GND_6") (pintype "passive"))
    )
    (net (code "66") (name "unconnected-(J1-RXI-Pad2)") (class "Default")
      (node (ref "J1") (pin "2") (pinfunction "RXI_2") (pintype "passive"))
    )
    (net (code "67") (name "unconnected-(J1-TXO-Pad3)") (class "Default")
      (node (ref "J1") (pin "3") (pinfunction "TXO_3") (pintype "passive"))
    )
    (net (code "68") (name "unconnected-(J1-VCC-Pad4)") (class "Default")
      (node (ref "J1") (pin "4") (pinfunction "VCC_4") (pintype "passive"))
    )
    (net (code "69") (name "unconnected-(J2-Pad1)") (class "Default")
      (node (ref "J2") (pin "1") (pinfunction "1_1") (pintype "passive"))
    )
    (net (code "70") (name "unconnected-(J2-Pad2)") (class "Default")
      (node (ref "J2") (pin "2") (pinfunction "2_2") (pintype "passive"))
    )
    (net (code "71") (name "unconnected-(J2-Pad3)") (class "Default")
      (node (ref "J2") (pin "3") (pinfunction "3_3") (pintype "passive"))
    )
    (net (code "72") (name "unconnected-(J2-Pad4)") (class "Default")
      (node (ref "J2") (pin "4") (pinfunction "4_4") (pintype "passive"))
    )
    (net (code "73") (name "unconnected-(J2-Pad5)") (class "Default")
      (node (ref "J2") (pin "5") (pinfunction "5_5") (pintype "passive"))
    )
    (net (code "74") (name "unconnected-(J2-Pad6)") (class "Default")
      (node (ref "J2") (pin "6") (pinfunction "6_6") (pintype "passive"))
    )
    (net (code "75") (name "unconnected-(J2-Pad7)") (class "Default")
      (node (ref "J2") (pin "7") (pinfunction "7_7") (pintype "passive"))
    )
    (net (code "76") (name "unconnected-(J2-Pad8)") (class "Default")
      (node (ref "J2") (pin "8") (pinfunction "8_8") (pintype "passive"))
    )
    (net (code "77") (name "unconnected-(J2-Pad9)") (class "Default")
      (node (ref "J2") (pin "9") (pinfunction "9_9") (pintype "passive"))
    )
    (net (code "78") (name "unconnected-(J2-Pad10)") (class "Default")
      (node (ref "J2") (pin "10") (pinfunction "10_10") (pintype "passive"))
    )
    (net (code "79") (name "unconnected-(J3-Pad1)") (class "Default")
      (node (ref "J3") (pin "1") (pinfunction "1_1") (pintype "passive"))
    )
    (net (code "80") (name "unconnected-(J3-Pad2)") (class "Default")
      (node (ref "J3") (pin "2") (pinfunction "2_2") (pintype "passive"))
    )
    (net (code "81") (name "unconnected-(J3-Pad3)") (class "Default")
      (node (ref "J3") (pin "3") (pinfunction "3_3") (pintype "passive"))
    )
    (net (code "82") (name "unconnected-(J3-Pad4)") (class "Default")
      (node (ref "J3") (pin "4") (pinfunction "4_4") (pintype "passive"))
    )
    (net (code "83") (name "unconnected-(J3-Pad5)") (class "Default")
      (node (ref "J3") (pin "5") (pinfunction "5_5") (pintype "passive"))
    )
    (net (code "84") (name "unconnected-(J3-Pad6)") (class "Default")
      (node (ref "J3") (pin "6") (pinfunction "6_6") (pintype "passive"))
    )
    (net (code "85") (name "unconnected-(J3-Pad7)") (class "Default")
      (node (ref "J3") (pin "7") (pinfunction "7_7") (pintype "passive"))
    )
    (net (code "86") (name "unconnected-(J3-Pad8)") (class "Default")
      (node (ref "J3") (pin "8") (pinfunction "8_8") (pintype "passive"))
    )
    (net (code "87") (name "unconnected-(J3-Pad9)") (class "Default")
      (node (ref "J3") (pin "9") (pinfunction "9_9") (pintype "passive"))
    )
    (net (code "88") (name "unconnected-(J3-Pad10)") (class "Default")
      (node (ref "J3") (pin "10") (pinfunction "10_10") (pintype "passive"))
    )
    (net (code "89") (name "unconnected-(J4-Pad1)") (class "Default")
      (node (ref "J4") (pin "1") (pinfunction "1_1") (pintype "passive"))
    )
    (net (code "90") (name "unconnected-(J4-Pad6)") (class "Default")
      (node (ref "J4") (pin "6") (pinfunction "6_6") (pintype "passive"))
    )
    (net (code "91") (name "unconnected-(J4-Pad7)") (class "Default")
      (node (ref "J4") (pin "7") (pinfunction "7_7") (pintype "passive"))
    )
    (net (code "92") (name "unconnected-(J4-Pad8)") (class "Default")
      (node (ref "J4") (pin "8") (pinfunction "8_8") (pintype "passive"))
    )
    (net (code "93") (name "unconnected-(J4-Pad9)") (class "Default")
      (node (ref "J4") (pin "9") (pinfunction "9_9") (pintype "passive"))
    )
    (net (code "94") (name "unconnected-(J4-Pad10)") (class "Default")
      (node (ref "J4") (pin "10") (pinfunction "10_10") (pintype "passive"))
    )
    (net (code "95") (name "unconnected-(J5-Pad1)") (class "Default")
      (node (ref "J5") (pin "1") (pinfunction "1_1") (pintype "passive"))
    )
    (net (code "96") (name "unconnected-(J6-Pad1)") (class "Default")
      (node (ref "J6") (pin "1") (pinfunction "1_1") (pintype "passive"))
    )
    (net (code "97") (name "unconnected-(J6-Pad2)") (class "Default")
      (node (ref "J6") (pin "2") (pinfunction "2_2") (pintype "passive"))
    )
    (net (code "98") (name "unconnected-(J6-Pad3)") (class "Default")
      (node (ref "J6") (pin "3") (pinfunction "3_3") (pintype "passive"))
    )
    (net (code "99") (name "unconnected-(J6-Pad4)") (class "Default")
      (node (ref "J6") (pin "4") (pinfunction "4_4") (pintype "passive"))
    )
    (net (code "100") (name "unconnected-(JP3-Pad1)") (class "Default")
      (node (ref "JP3") (pin "1") (pinfunction "1_1") (pintype "passive"))
    )
    (net (code "101") (name "unconnected-(JP4-Pad1)") (class "Default")
      (node (ref "JP4") (pin "1") (pinfunction "1_1") (pintype "passive"))
    )
  )
)
